# Integrated_Main_Driver_Board-05-Wireless.net
KiCad netlist of a schematic drawn in Altium Designer
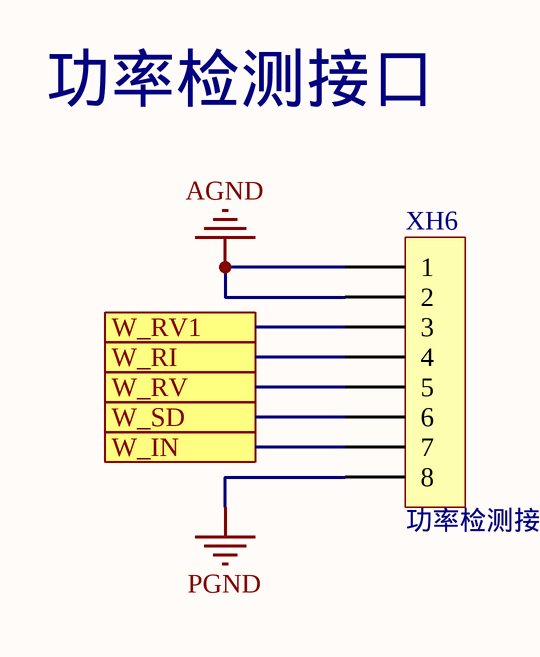
[diagram p0: Integrated_Main_Driver_Board-05-Wireless Charging Circuit-20230110.SchDoc]

(export (version "E")
  (design (tool "Eeschema 10.0.6"))
  (components
    (comp (ref "XH6") (value "功率检测接口") (footprint "XH8/2.54mm/180") (libsource (lib "XH，VH") (part "XH8")))
  )
  (nets
    (net (code "1") (name "/W_IN") (class "Default")
      (node (ref "XH6") (pin "7") (pinfunction "7_7") (pintype "passive"))
    )
    (net (code "2") (name "/W_RI") (class "Default")
      (node (ref "XH6") (pin "4") (pinfunction "4_4") (pintype "passive"))
    )
    (net (code "3") (name "/W_RV") (class "Default")
      (node (ref "XH6") (pin "5") (pinfunction "5_5") (pintype "passive"))
    )
    (net (code "4") (name "/W_RV1") (class "Default")
      (node (ref "XH6") (pin "3") (pinfunction "3_3") (pintype "passive"))
    )
    (net (code "5") (name "/W_SD") (class "Default")
      (node (ref "XH6") (pin "6") (pinfunction "6_6") (pintype "passive"))
    )
    (net (code "6") (name "AGND") (class "Default")
      (node (ref "XH6") (pin "1") (pinfunction "1_1") (pintype "passive"))
      (node (ref "XH6") (pin "2") (pinfunction "2_2") (pintype "passive"))
    )
    (net (code "7") (name "PGND") (class "Default")
      (node (ref "XH6") (pin "8") (pinfunction "8_8") (pintype "passive"))
    )
  )
)
